# usb_to_uart_converter.net
KiCad netlist of a schematic drawn in EAGLE
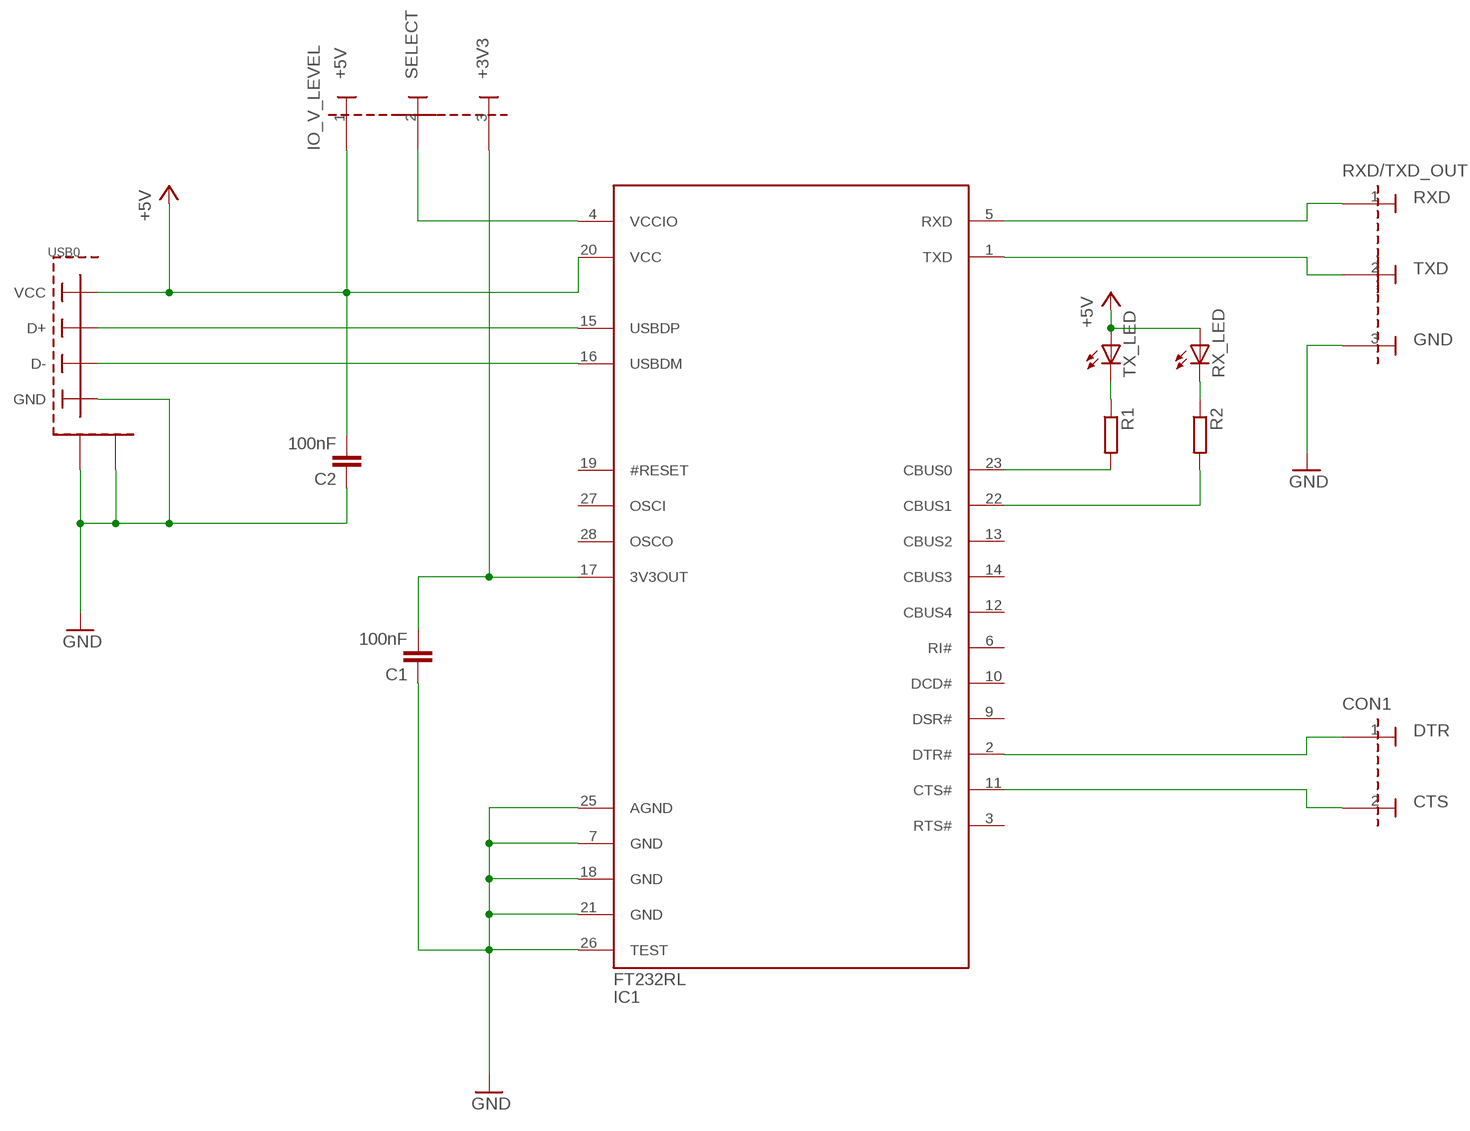
[diagram p0: schematic, sheet 1]

(export (version "E")
  (design (tool "Eeschema 10.0.6"))
  (components
    (comp (ref "C1")
      (value "100nF")
      (footprint "eagle-import:C0805")
      (libsource (lib "eagle-import") (part "C-EUC0805"))
    )
    (comp (ref "C2")
      (value "100nF")
      (footprint "eagle-import:C0805")
      (libsource (lib "eagle-import") (part "C-EUC0805"))
    )
    (comp (ref "CON1")
      (value "CONNECTOR_2PIN1X2")
      (footprint "eagle-import:1X2_GENERIC")
      (fields (field (name "PIN1") "DTR") (field (name "PIN2") "CTS"))
      (libsource (lib "eagle-import") (part "CONNECTOR_2PIN1X2"))
    )
    (comp (ref "IC1")
      (value "FT232RL")
      (footprint "eagle-import:SSOP28")
      (libsource (lib "eagle-import") (part "FT232RL"))
    )
    (comp (ref "IO_V_LEVEL")
      (value "CONNECTOR_3PINWITH_LABELS")
      (footprint "eagle-import:1X3_GENERIC_WITH_LABELS")
      (fields (field (name "PIN1") "+5V") (field (name "PIN2") "SELECT") (field (name "PIN3") "+3V3"))
      (libsource (lib "eagle-import") (part "CONNECTOR_3PINWITH_LABELS"))
    )
    (comp (ref "R1")
      (value "R-EU_R0805")
      (footprint "eagle-import:R0805")
      (libsource (lib "eagle-import") (part "R-EU_R0805"))
    )
    (comp (ref "R2")
      (value "R-EU_R0805")
      (footprint "eagle-import:R0805")
      (libsource (lib "eagle-import") (part "R-EU_R0805"))
    )
    (comp (ref "RXD/TXD_OUT")
      (value "CONNECTOR_3PINWITH_LABELS")
      (footprint "eagle-import:1X3_GENERIC_WITH_LABELS")
      (fields (field (name "PIN1") "RXD") (field (name "PIN2") "TXD") (field (name "PIN3") "GND"))
      (libsource (lib "eagle-import") (part "CONNECTOR_3PINWITH_LABELS"))
    )
    (comp (ref "RX_LED")
      (value "LED_LIBCHIPLED_0805")
      (footprint "eagle-import:CHIPLED_0805")
      (libsource (lib "eagle-import") (part "LED_LIBCHIPLED_0805"))
    )
    (comp (ref "TX_LED")
      (value "LED_LIBCHIPLED_0805")
      (footprint "eagle-import:CHIPLED_0805")
      (libsource (lib "eagle-import") (part "LED_LIBCHIPLED_0805"))
    )
    (comp (ref "USB0")
      (value "USB-BWUERTH-ELECTRONIC-USB-B")
      (footprint "eagle-import:USB-B-THROUGH-HOLE")
      (libsource (lib "eagle-import") (part "USB-BWUERTH-ELECTRONIC-USB-B"))
    )
  )
  (nets
    (net (code "1") (name "+5V") (class "Default")
      (node (ref "C2") (pin "2") (pinfunction "2_2") (pintype "passive"))
      (node (ref "IC1") (pin "20") (pinfunction "VCC_20") (pintype "bidirectional"))
      (node (ref "IO_V_LEVEL") (pin "1") (pinfunction "P$1_1") (pintype "bidirectional"))
      (node (ref "RX_LED") (pin "A") (pinfunction "A_A") (pintype "passive"))
      (node (ref "TX_LED") (pin "A") (pinfunction "A_A") (pintype "passive"))
      (node (ref "USB0") (pin "VCC") (pinfunction "VCC_VCC") (pintype "bidirectional"))
    )
    (net (code "2") (name "GND") (class "Default")
      (node (ref "C1") (pin "1") (pinfunction "1_1") (pintype "passive"))
      (node (ref "C2") (pin "1") (pinfunction "1_1") (pintype "passive"))
      (node (ref "IC1") (pin "18") (pinfunction "GND_18") (pintype "bidirectional"))
      (node (ref "IC1") (pin "21") (pinfunction "GND_21") (pintype "bidirectional"))
      (node (ref "IC1") (pin "25") (pinfunction "AGND_25") (pintype "bidirectional"))
      (node (ref "IC1") (pin "26") (pinfunction "TEST_26") (pintype "bidirectional"))
      (node (ref "IC1") (pin "7") (pinfunction "GND_7") (pintype "bidirectional"))
      (node (ref "RXD/TXD_OUT") (pin "3") (pinfunction "P$3_3") (pintype "bidirectional"))
      (node (ref "USB0") (pin "GND") (pinfunction "GND_GND") (pintype "bidirectional"))
      (node (ref "USB0") (pin "SHIELD") (pinfunction "SHIELD_SHIELD") (pintype "bidirectional"))
      (node (ref "USB0") (pin "SHIELD@2") (pinfunction "SHIELD_SHIELD@2") (pintype "bidirectional"))
    )
    (net (code "3") (name "Net-(CON1-P$1)") (class "Default")
      (node (ref "CON1") (pin "1") (pinfunction "P$1_1") (pintype "bidirectional"))
      (node (ref "IC1") (pin "2") (pinfunction "DTR#_2") (pintype "bidirectional"))
    )
    (net (code "4") (name "Net-(CON1-P$2)") (class "Default")
      (node (ref "CON1") (pin "2") (pinfunction "P$2_2") (pintype "bidirectional"))
      (node (ref "IC1") (pin "11") (pinfunction "CTS#_11") (pintype "bidirectional"))
    )
    (net (code "5") (name "Net-(IC1-3V3OUT)") (class "Default")
      (node (ref "C1") (pin "2") (pinfunction "2_2") (pintype "passive"))
      (node (ref "IC1") (pin "17") (pinfunction "3V3OUT_17") (pintype "bidirectional"))
      (node (ref "IO_V_LEVEL") (pin "3") (pinfunction "P$3_3") (pintype "bidirectional"))
    )
    (net (code "6") (name "Net-(IC1-CBUS0)") (class "Default")
      (node (ref "IC1") (pin "23") (pinfunction "CBUS0_23") (pintype "bidirectional"))
      (node (ref "R1") (pin "2") (pinfunction "2_2") (pintype "passive"))
    )
    (net (code "7") (name "Net-(IC1-CBUS1)") (class "Default")
      (node (ref "IC1") (pin "22") (pinfunction "CBUS1_22") (pintype "bidirectional"))
      (node (ref "R2") (pin "2") (pinfunction "2_2") (pintype "passive"))
    )
    (net (code "8") (name "Net-(IC1-RXD)") (class "Default")
      (node (ref "IC1") (pin "5") (pinfunction "RXD_5") (pintype "bidirectional"))
      (node (ref "RXD/TXD_OUT") (pin "1") (pinfunction "P$1_1") (pintype "bidirectional"))
    )
    (net (code "9") (name "Net-(IC1-TXD)") (class "Default")
      (node (ref "IC1") (pin "1") (pinfunction "TXD_1") (pintype "bidirectional"))
      (node (ref "RXD/TXD_OUT") (pin "2") (pinfunction "P$2_2") (pintype "bidirectional"))
    )
    (net (code "10") (name "Net-(IC1-USBDM)") (class "Default")
      (node (ref "IC1") (pin "16") (pinfunction "USBDM_16") (pintype "bidirectional"))
      (node (ref "USB0") (pin "D-") (pinfunction "D-_D-") (pintype "bidirectional"))
    )
    (net (code "11") (name "Net-(IC1-USBDP)") (class "Default")
      (node (ref "IC1") (pin "15") (pinfunction "USBDP_15") (pintype "bidirectional"))
      (node (ref "USB0") (pin "D+") (pinfunction "D+_D+") (pintype "bidirectional"))
    )
    (net (code "12") (name "Net-(IC1-VCCIO)") (class "Default")
      (node (ref "IC1") (pin "4") (pinfunction "VCCIO_4") (pintype "bidirectional"))
      (node (ref "IO_V_LEVEL") (pin "2") (pinfunction "P$2_2") (pintype "bidirectional"))
    )
    (net (code "13") (name "Net-(R1-Pad1)") (class "Default")
      (node (ref "R1") (pin "1") (pinfunction "1_1") (pintype "passive"))
      (node (ref "TX_LED") (pin "C") (pinfunction "C_C") (pintype "passive"))
    )
    (net (code "14") (name "Net-(R2-Pad1)") (class "Default")
      (node (ref "R2") (pin "1") (pinfunction "1_1") (pintype "passive"))
      (node (ref "RX_LED") (pin "C") (pinfunction "C_C") (pintype "passive"))
    )
    (net (code "15") (name "unconnected-(IC1-#RESET-Pad19)") (class "Default")
      (node (ref "IC1") (pin "19") (pinfunction "#RESET_19") (pintype "bidirectional"))
    )
    (net (code "16") (name "unconnected-(IC1-CBUS2-Pad13)") (class "Default")
      (node (ref "IC1") (pin "13") (pinfunction "CBUS2_13") (pintype "bidirectional"))
    )
    (net (code "17") (name "unconnected-(IC1-CBUS3-Pad14)") (class "Default")
      (node (ref "IC1") (pin "14") (pinfunction "CBUS3_14") (pintype "bidirectional"))
    )
    (net (code "18") (name "unconnected-(IC1-CBUS4-Pad12)") (class "Default")
      (node (ref "IC1") (pin "12") (pinfunction "CBUS4_12") (pintype "bidirectional"))
    )
    (net (code "19") (name "unconnected-(IC1-DCD#-Pad10)") (class "Default")
      (node (ref "IC1") (pin "10") (pinfunction "DCD#_10") (pintype "bidirectional"))
    )
    (net (code "20") (name "unconnected-(IC1-DSR#-Pad9)") (class "Default")
      (node (ref "IC1") (pin "9") (pinfunction "DSR#_9") (pintype "bidirectional"))
    )
    (net (code "21") (name "unconnected-(IC1-OSCI-Pad27)") (class "Default")
      (node (ref "IC1") (pin "27") (pinfunction "OSCI_27") (pintype "bidirectional"))
    )
    (net (code "22") (name "unconnected-(IC1-OSCO-Pad28)") (class "Default")
      (node (ref "IC1") (pin "28") (pinfunction "OSCO_28") (pintype "bidirectional"))
    )
    (net (code "23") (name "unconnected-(IC1-RI#-Pad6)") (class "Default")
      (node (ref "IC1") (pin "6") (pinfunction "RI#_6") (pintype "bidirectional"))
    )
    (net (code "24") (name "unconnected-(IC1-RTS#-Pad3)") (class "Default")
      (node (ref "IC1") (pin "3") (pinfunction "RTS#_3") (pintype "bidirectional"))
    )
  )
)
